# grbl_nano_my_clone_PR3.net
KiCad netlist of a schematic drawn in EAGLE
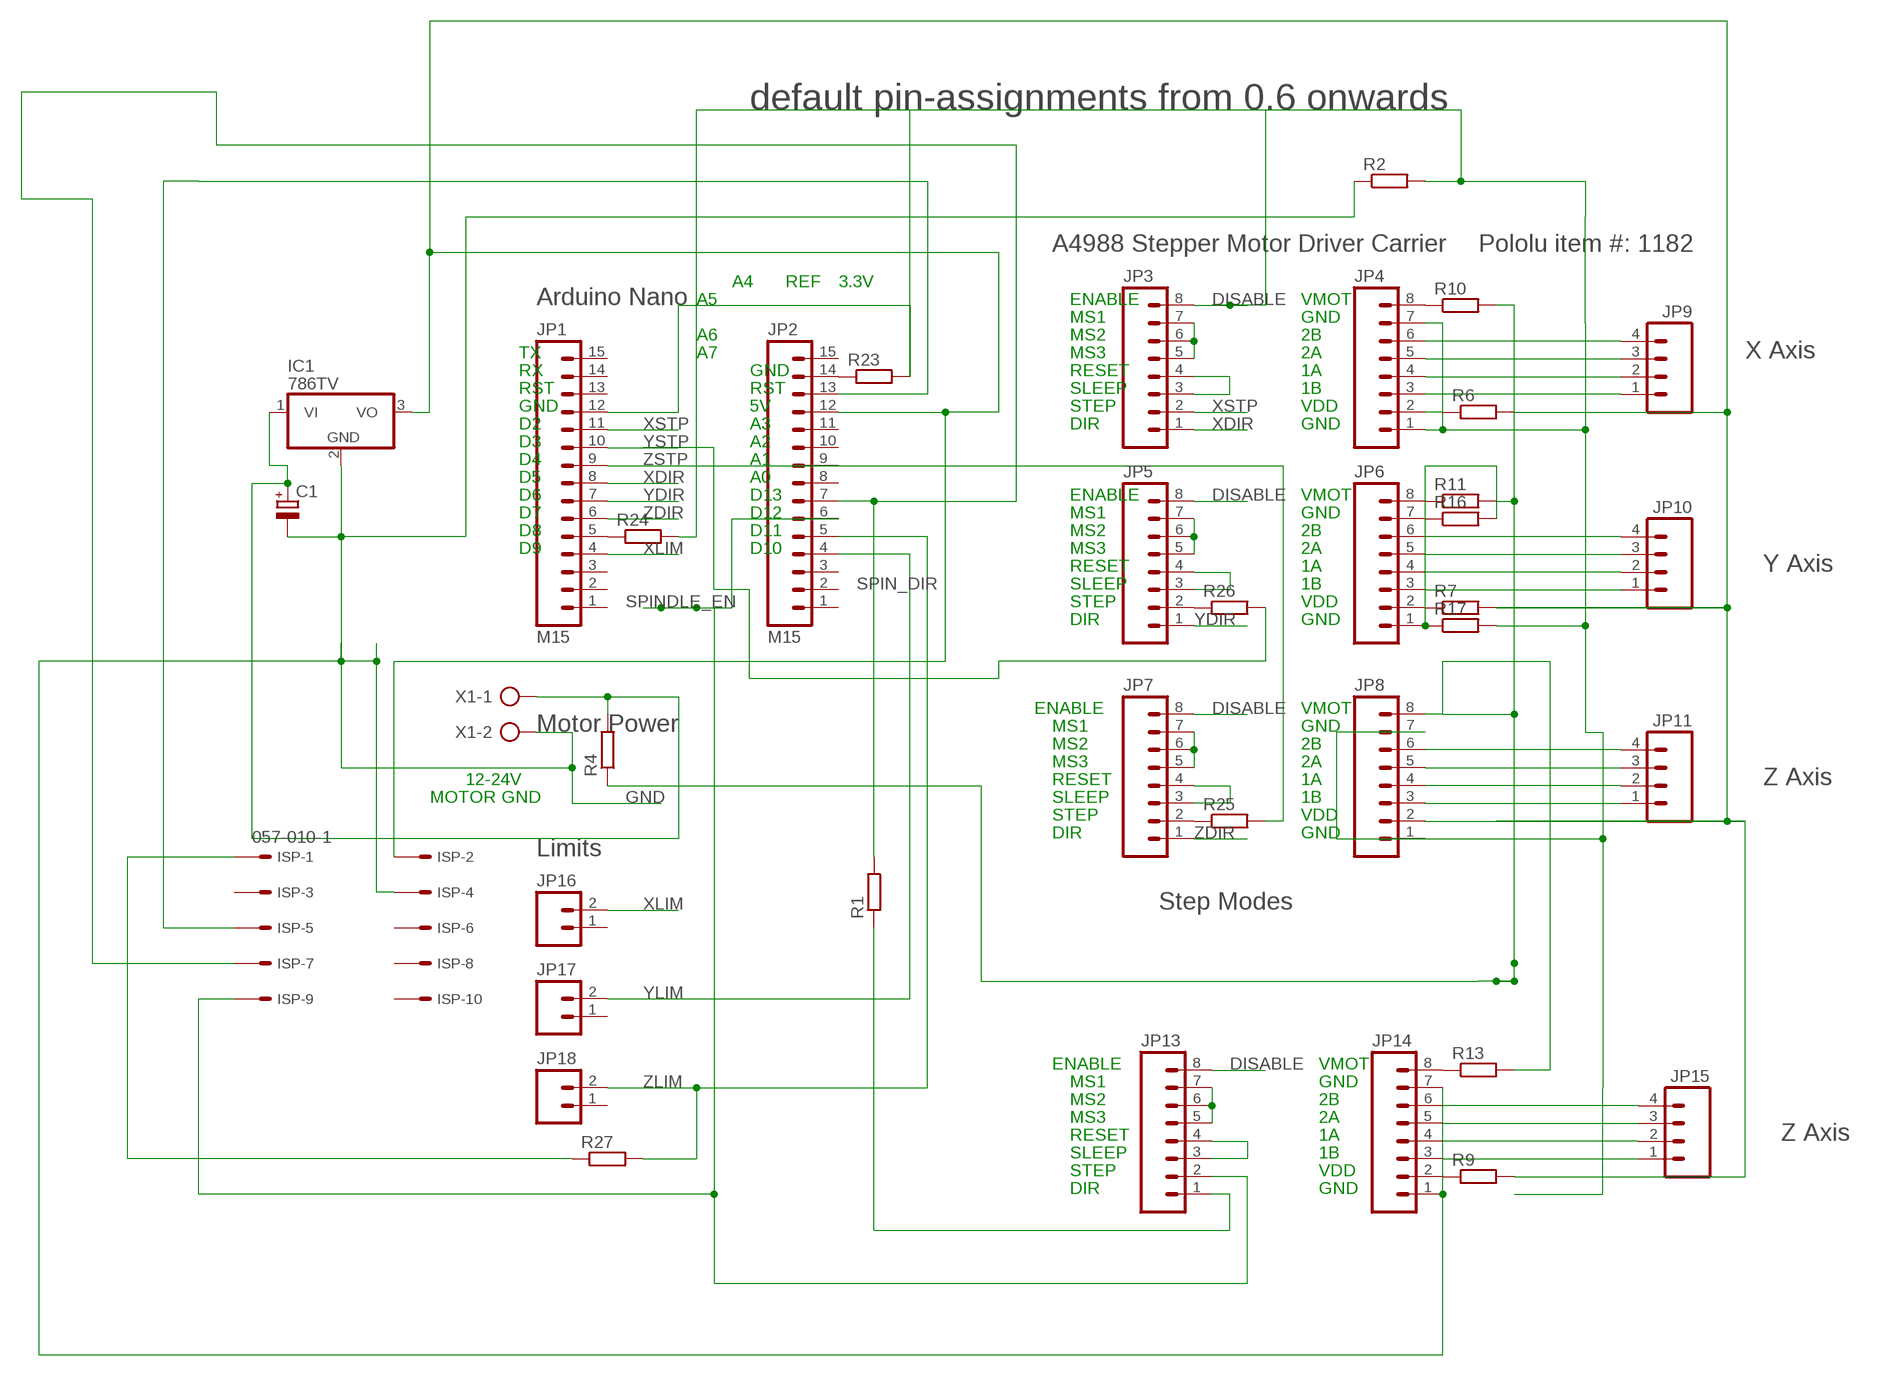
[diagram p0: schematic, sheet 1]

(export (version "E")
  (design (tool "Eeschema 10.0.6"))
  (components
    (comp (ref "C1")
      (value "CPOL-EUE3.5-8")
      (footprint "eagle-import:E3,5-8")
      (libsource (lib "eagle-import") (part "CPOL-EUE3.5-8"))
    )
    (comp (ref "IC1")
      (value "786TV")
      (footprint "eagle-import:TO220V")
      (libsource (lib "eagle-import") (part "78TV6"))
    )
    (comp (ref "ISP")
      (value "057-010-1")
      (footprint "eagle-import:057-010-1")
      (libsource (lib "eagle-import") (part "057-010-1"))
    )
    (comp (ref "JP1")
      (value "M15")
      (footprint "eagle-import:1X15")
      (libsource (lib "eagle-import") (part "M15"))
    )
    (comp (ref "JP2")
      (value "M15")
      (footprint "eagle-import:1X15")
      (libsource (lib "eagle-import") (part "M15"))
    )
    (comp (ref "JP3")
      (value "M08LONGPADS")
      (footprint "eagle-import:1X08_LONGPADS")
      (libsource (lib "eagle-import") (part "M08LONGPADS"))
    )
    (comp (ref "JP4")
      (value "M08LONGPADS")
      (footprint "eagle-import:1X08_LONGPADS")
      (libsource (lib "eagle-import") (part "M08LONGPADS"))
    )
    (comp (ref "JP5")
      (value "M08LONGPADS")
      (footprint "eagle-import:1X08_LONGPADS")
      (libsource (lib "eagle-import") (part "M08LONGPADS"))
    )
    (comp (ref "JP6")
      (value "M08LONGPADS")
      (footprint "eagle-import:1X08_LONGPADS")
      (libsource (lib "eagle-import") (part "M08LONGPADS"))
    )
    (comp (ref "JP7")
      (value "M08LONGPADS")
      (footprint "eagle-import:1X08_LONGPADS")
      (libsource (lib "eagle-import") (part "M08LONGPADS"))
    )
    (comp (ref "JP8")
      (value "M08LONGPADS")
      (footprint "eagle-import:1X08_LONGPADS")
      (libsource (lib "eagle-import") (part "M08LONGPADS"))
    )
    (comp (ref "JP9")
      (value "M04LONGPADS")
      (footprint "eagle-import:1X04_LONGPADS")
      (libsource (lib "eagle-import") (part "M04LONGPADS"))
    )
    (comp (ref "JP10")
      (value "M04LONGPADS")
      (footprint "eagle-import:1X04_LONGPADS")
      (libsource (lib "eagle-import") (part "M04LONGPADS"))
    )
    (comp (ref "JP11")
      (value "M04LONGPADS")
      (footprint "eagle-import:1X04_LONGPADS")
      (libsource (lib "eagle-import") (part "M04LONGPADS"))
    )
    (comp (ref "JP13")
      (value "M08LONGPADS")
      (footprint "eagle-import:1X08_LONGPADS")
      (libsource (lib "eagle-import") (part "M08LONGPADS"))
    )
    (comp (ref "JP14")
      (value "M08LONGPADS")
      (footprint "eagle-import:1X08_LONGPADS")
      (libsource (lib "eagle-import") (part "M08LONGPADS"))
    )
    (comp (ref "JP15")
      (value "M04LONGPADS")
      (footprint "eagle-import:1X04_LONGPADS")
      (libsource (lib "eagle-import") (part "M04LONGPADS"))
    )
    (comp (ref "JP16")
      (value "M02LOCK_LONGPADS")
      (footprint "eagle-import:1X02_LOCK_LONGPADS")
      (libsource (lib "eagle-import") (part "M02LOCK_LONGPADS"))
    )
    (comp (ref "JP17")
      (value "M02LOCK_LONGPADS")
      (footprint "eagle-import:1X02_LOCK_LONGPADS")
      (libsource (lib "eagle-import") (part "M02LOCK_LONGPADS"))
    )
    (comp (ref "JP18")
      (value "M02LOCK_LONGPADS")
      (footprint "eagle-import:1X02_LOCK_LONGPADS")
      (libsource (lib "eagle-import") (part "M02LOCK_LONGPADS"))
    )
    (comp (ref "R1")
      (value "R-EU_0207/15")
      (footprint "eagle-import:0207_15")
      (libsource (lib "eagle-import") (part "R-EU_0207/15"))
    )
    (comp (ref "R2")
      (value "R-EU_0207/15")
      (footprint "eagle-import:0207_15")
      (libsource (lib "eagle-import") (part "R-EU_0207/15"))
    )
    (comp (ref "R4")
      (value "R-EU_0207/12")
      (footprint "eagle-import:0207_12")
      (libsource (lib "eagle-import") (part "R-EU_0207/12"))
    )
    (comp (ref "R6")
      (value "R-EU_0207/15")
      (footprint "eagle-import:0207_15")
      (libsource (lib "eagle-import") (part "R-EU_0207/15"))
    )
    (comp (ref "R7")
      (value "R-EU_0207/15")
      (footprint "eagle-import:0207_15")
      (libsource (lib "eagle-import") (part "R-EU_0207/15"))
    )
    (comp (ref "R9")
      (value "R-EU_0207/15")
      (footprint "eagle-import:0207_15")
      (libsource (lib "eagle-import") (part "R-EU_0207/15"))
    )
    (comp (ref "R10")
      (value "R-EU_0207/7")
      (footprint "eagle-import:0207_7")
      (libsource (lib "eagle-import") (part "R-EU_0207/7"))
    )
    (comp (ref "R11")
      (value "R-EU_0207/7")
      (footprint "eagle-import:0207_7")
      (libsource (lib "eagle-import") (part "R-EU_0207/7"))
    )
    (comp (ref "R13")
      (value "R-EU_0207/15")
      (footprint "eagle-import:0207_15")
      (libsource (lib "eagle-import") (part "R-EU_0207/15"))
    )
    (comp (ref "R16")
      (value "R-EU_0207/12")
      (footprint "eagle-import:0207_12")
      (libsource (lib "eagle-import") (part "R-EU_0207/12"))
    )
    (comp (ref "R17")
      (value "R-EU_0207/12")
      (footprint "eagle-import:0207_12")
      (libsource (lib "eagle-import") (part "R-EU_0207/12"))
    )
    (comp (ref "R23")
      (value "R-EU_0207/15")
      (footprint "eagle-import:0207_15")
      (libsource (lib "eagle-import") (part "R-EU_0207/15"))
    )
    (comp (ref "R24")
      (value "R-EU_0207/15")
      (footprint "eagle-import:0207_15")
      (libsource (lib "eagle-import") (part "R-EU_0207/15"))
    )
    (comp (ref "R25")
      (value "R-EU_0207/15")
      (footprint "eagle-import:0207_15")
      (libsource (lib "eagle-import") (part "R-EU_0207/15"))
    )
    (comp (ref "R26")
      (value "R-EU_0207/15")
      (footprint "eagle-import:0207_15")
      (libsource (lib "eagle-import") (part "R-EU_0207/15"))
    )
    (comp (ref "R27")
      (value "R-EU_0207/15")
      (footprint "eagle-import:0207_15")
      (libsource (lib "eagle-import") (part "R-EU_0207/15"))
    )
    (comp (ref "X1")
      (value "AK300/2")
      (footprint "eagle-import:AK300_2")
      (libsource (lib "eagle-import") (part "AK300/2"))
    )
  )
  (nets
    (net (code "1") (name "/DISABLE") (class "Default")
      (node (ref "JP13") (pin "8") (pinfunction "8_8") (pintype "passive"))
      (node (ref "JP3") (pin "8") (pinfunction "8_8") (pintype "passive"))
      (node (ref "JP5") (pin "8") (pinfunction "8_8") (pintype "passive"))
      (node (ref "JP7") (pin "8") (pinfunction "8_8") (pintype "passive"))
      (node (ref "R24") (pin "2") (pinfunction "2_2") (pintype "passive"))
    )
    (net (code "2") (name "/GND") (class "Default")
      (node (ref "C1") (pin "-") (pinfunction "-_-") (pintype "passive"))
      (node (ref "IC1") (pin "2") (pinfunction "GND_2") (pintype "passive"))
      (node (ref "ISP") (pin "4") (pinfunction "S_4") (pintype "passive"))
      (node (ref "JP14") (pin "1") (pinfunction "1_1") (pintype "passive"))
      (node (ref "JP14") (pin "7") (pinfunction "7_7") (pintype "passive"))
      (node (ref "R2") (pin "1") (pinfunction "1_1") (pintype "passive"))
      (node (ref "X1") (pin "2") (pinfunction "KL_2") (pintype "passive"))
    )
    (net (code "3") (name "/SPINDLE_EN") (class "Default")
      (node (ref "ISP") (pin "9") (pinfunction "S_9") (pintype "passive"))
      (node (ref "JP13") (pin "2") (pinfunction "2_2") (pintype "passive"))
      (node (ref "JP2") (pin "6") (pinfunction "6_6") (pintype "passive"))
    )
    (net (code "5") (name "/SPIN_DIR") (class "Default")
      (node (ref "ISP") (pin "7") (pinfunction "S_7") (pintype "passive"))
      (node (ref "JP2") (pin "7") (pinfunction "7_7") (pintype "passive"))
      (node (ref "R1") (pin "2") (pinfunction "2_2") (pintype "passive"))
    )
    (net (code "6") (name "/XDIR") (class "Default")
      (node (ref "JP1") (pin "8") (pinfunction "8_8") (pintype "passive"))
      (node (ref "JP3") (pin "1") (pinfunction "1_1") (pintype "passive"))
    )
    (net (code "7") (name "/XLIM") (class "Default")
      (node (ref "JP1") (pin "4") (pinfunction "4_4") (pintype "passive"))
      (node (ref "JP16") (pin "2") (pinfunction "2_2") (pintype "passive"))
    )
    (net (code "8") (name "/XSTP") (class "Default")
      (node (ref "JP1") (pin "11") (pinfunction "11_11") (pintype "passive"))
      (node (ref "JP3") (pin "2") (pinfunction "2_2") (pintype "passive"))
    )
    (net (code "9") (name "/YDIR") (class "Default")
      (node (ref "JP1") (pin "7") (pinfunction "7_7") (pintype "passive"))
      (node (ref "JP5") (pin "1") (pinfunction "1_1") (pintype "passive"))
    )
    (net (code "10") (name "/YLIM") (class "Default")
      (node (ref "JP17") (pin "2") (pinfunction "2_2") (pintype "passive"))
      (node (ref "JP2") (pin "4") (pinfunction "4_4") (pintype "passive"))
    )
    (net (code "11") (name "/YSTP") (class "Default")
      (node (ref "JP1") (pin "10") (pinfunction "10_10") (pintype "passive"))
      (node (ref "R26") (pin "2") (pinfunction "2_2") (pintype "passive"))
    )
    (net (code "12") (name "/ZDIR") (class "Default")
      (node (ref "JP1") (pin "6") (pinfunction "6_6") (pintype "passive"))
      (node (ref "JP7") (pin "1") (pinfunction "1_1") (pintype "passive"))
    )
    (net (code "13") (name "/ZLIM") (class "Default")
      (node (ref "JP18") (pin "2") (pinfunction "2_2") (pintype "passive"))
      (node (ref "JP2") (pin "5") (pinfunction "5_5") (pintype "passive"))
      (node (ref "R27") (pin "2") (pinfunction "2_2") (pintype "passive"))
    )
    (net (code "14") (name "/ZSTP") (class "Default")
      (node (ref "JP1") (pin "9") (pinfunction "9_9") (pintype "passive"))
      (node (ref "R25") (pin "2") (pinfunction "2_2") (pintype "passive"))
    )
    (net (code "15") (name "Net-(IC1-VI)") (class "Default")
      (node (ref "C1") (pin "+") (pinfunction "+_+") (pintype "passive"))
      (node (ref "IC1") (pin "1") (pinfunction "VI_1") (pintype "input"))
      (node (ref "R4") (pin "2") (pinfunction "2_2") (pintype "passive"))
      (node (ref "X1") (pin "1") (pinfunction "KL_1") (pintype "passive"))
    )
    (net (code "16") (name "Net-(IC1-VO)") (class "Default")
      (node (ref "IC1") (pin "3") (pinfunction "VO_3") (pintype "passive"))
      (node (ref "ISP") (pin "2") (pinfunction "S_2") (pintype "passive"))
      (node (ref "JP2") (pin "12") (pinfunction "12_12") (pintype "passive"))
      (node (ref "JP8") (pin "2") (pinfunction "2_2") (pintype "passive"))
      (node (ref "R6") (pin "2") (pinfunction "2_2") (pintype "passive"))
      (node (ref "R7") (pin "2") (pinfunction "2_2") (pintype "passive"))
      (node (ref "R9") (pin "2") (pinfunction "2_2") (pintype "passive"))
    )
    (net (code "17") (name "Net-(ISPA-S)") (class "Default")
      (node (ref "ISP") (pin "1") (pinfunction "S_1") (pintype "passive"))
      (node (ref "R27") (pin "1") (pinfunction "1_1") (pintype "passive"))
    )
    (net (code "18") (name "Net-(ISPF-S)") (class "Default")
      (node (ref "ISP") (pin "5") (pinfunction "S_5") (pintype "passive"))
      (node (ref "JP2") (pin "13") (pinfunction "13_13") (pintype "passive"))
    )
    (net (code "19") (name "Net-(JP1-Pad5)") (class "Default")
      (node (ref "JP1") (pin "5") (pinfunction "5_5") (pintype "passive"))
      (node (ref "R24") (pin "1") (pinfunction "1_1") (pintype "passive"))
    )
    (net (code "20") (name "Net-(JP1-Pad12)") (class "Default")
      (node (ref "JP1") (pin "12") (pinfunction "12_12") (pintype "passive"))
      (node (ref "JP4") (pin "1") (pinfunction "1_1") (pintype "passive"))
      (node (ref "JP4") (pin "7") (pinfunction "7_7") (pintype "passive"))
      (node (ref "JP8") (pin "1") (pinfunction "1_1") (pintype "passive"))
      (node (ref "JP8") (pin "7") (pinfunction "7_7") (pintype "passive"))
      (node (ref "R17") (pin "2") (pinfunction "2_2") (pintype "passive"))
      (node (ref "R2") (pin "2") (pinfunction "2_2") (pintype "passive"))
      (node (ref "R23") (pin "2") (pinfunction "2_2") (pintype "passive"))
    )
    (net (code "21") (name "Net-(JP2-Pad14)") (class "Default")
      (node (ref "JP2") (pin "14") (pinfunction "14_14") (pintype "passive"))
      (node (ref "R23") (pin "1") (pinfunction "1_1") (pintype "passive"))
    )
    (net (code "22") (name "Net-(JP3-Pad3)") (class "Default")
      (node (ref "JP3") (pin "3") (pinfunction "3_3") (pintype "passive"))
      (node (ref "JP3") (pin "4") (pinfunction "4_4") (pintype "passive"))
    )
    (net (code "23") (name "Net-(JP3-Pad5)") (class "Default")
      (node (ref "JP3") (pin "5") (pinfunction "5_5") (pintype "passive"))
      (node (ref "JP3") (pin "6") (pinfunction "6_6") (pintype "passive"))
      (node (ref "JP3") (pin "7") (pinfunction "7_7") (pintype "passive"))
    )
    (net (code "24") (name "Net-(JP4-Pad2)") (class "Default")
      (node (ref "JP4") (pin "2") (pinfunction "2_2") (pintype "passive"))
      (node (ref "R6") (pin "1") (pinfunction "1_1") (pintype "passive"))
    )
    (net (code "25") (name "Net-(JP4-Pad3)") (class "Default")
      (node (ref "JP4") (pin "3") (pinfunction "3_3") (pintype "passive"))
      (node (ref "JP9") (pin "1") (pinfunction "1_1") (pintype "passive"))
    )
    (net (code "26") (name "Net-(JP4-Pad4)") (class "Default")
      (node (ref "JP4") (pin "4") (pinfunction "4_4") (pintype "passive"))
      (node (ref "JP9") (pin "2") (pinfunction "2_2") (pintype "passive"))
    )
    (net (code "27") (name "Net-(JP4-Pad5)") (class "Default")
      (node (ref "JP4") (pin "5") (pinfunction "5_5") (pintype "passive"))
      (node (ref "JP9") (pin "3") (pinfunction "3_3") (pintype "passive"))
    )
    (net (code "28") (name "Net-(JP4-Pad6)") (class "Default")
      (node (ref "JP4") (pin "6") (pinfunction "6_6") (pintype "passive"))
      (node (ref "JP9") (pin "4") (pinfunction "4_4") (pintype "passive"))
    )
    (net (code "29") (name "Net-(JP4-Pad8)") (class "Default")
      (node (ref "JP4") (pin "8") (pinfunction "8_8") (pintype "passive"))
      (node (ref "R10") (pin "1") (pinfunction "1_1") (pintype "passive"))
    )
    (net (code "30") (name "Net-(JP5-Pad2)") (class "Default")
      (node (ref "JP5") (pin "2") (pinfunction "2_2") (pintype "passive"))
      (node (ref "R26") (pin "1") (pinfunction "1_1") (pintype "passive"))
    )
    (net (code "31") (name "Net-(JP5-Pad3)") (class "Default")
      (node (ref "JP5") (pin "3") (pinfunction "3_3") (pintype "passive"))
      (node (ref "JP5") (pin "4") (pinfunction "4_4") (pintype "passive"))
    )
    (net (code "32") (name "Net-(JP5-Pad5)") (class "Default")
      (node (ref "JP5") (pin "5") (pinfunction "5_5") (pintype "passive"))
      (node (ref "JP5") (pin "6") (pinfunction "6_6") (pintype "passive"))
      (node (ref "JP5") (pin "7") (pinfunction "7_7") (pintype "passive"))
    )
    (net (code "33") (name "Net-(JP6-Pad1)") (class "Default")
      (node (ref "JP6") (pin "1") (pinfunction "1_1") (pintype "passive"))
      (node (ref "R16") (pin "2") (pinfunction "2_2") (pintype "passive"))
      (node (ref "R17") (pin "1") (pinfunction "1_1") (pintype "passive"))
    )
    (net (code "34") (name "Net-(JP6-Pad2)") (class "Default")
      (node (ref "JP6") (pin "2") (pinfunction "2_2") (pintype "passive"))
      (node (ref "R7") (pin "1") (pinfunction "1_1") (pintype "passive"))
    )
    (net (code "35") (name "Net-(JP6-Pad7)") (class "Default")
      (node (ref "JP6") (pin "7") (pinfunction "7_7") (pintype "passive"))
      (node (ref "R16") (pin "1") (pinfunction "1_1") (pintype "passive"))
    )
    (net (code "36") (name "Net-(JP6-Pad8)") (class "Default")
      (node (ref "JP6") (pin "8") (pinfunction "8_8") (pintype "passive"))
      (node (ref "R11") (pin "1") (pinfunction "1_1") (pintype "passive"))
    )
    (net (code "37") (name "Net-(JP7-Pad2)") (class "Default")
      (node (ref "JP7") (pin "2") (pinfunction "2_2") (pintype "passive"))
      (node (ref "R25") (pin "1") (pinfunction "1_1") (pintype "passive"))
    )
    (net (code "38") (name "Net-(JP7-Pad3)") (class "Default")
      (node (ref "JP7") (pin "3") (pinfunction "3_3") (pintype "passive"))
      (node (ref "JP7") (pin "4") (pinfunction "4_4") (pintype "passive"))
    )
    (net (code "39") (name "Net-(JP7-Pad5)") (class "Default")
      (node (ref "JP7") (pin "5") (pinfunction "5_5") (pintype "passive"))
      (node (ref "JP7") (pin "6") (pinfunction "6_6") (pintype "passive"))
      (node (ref "JP7") (pin "7") (pinfunction "7_7") (pintype "passive"))
    )
    (net (code "40") (name "Net-(JP8-Pad8)") (class "Default")
      (node (ref "JP8") (pin "8") (pinfunction "8_8") (pintype "passive"))
      (node (ref "R10") (pin "2") (pinfunction "2_2") (pintype "passive"))
      (node (ref "R11") (pin "2") (pinfunction "2_2") (pintype "passive"))
      (node (ref "R13") (pin "2") (pinfunction "2_2") (pintype "passive"))
      (node (ref "R4") (pin "1") (pinfunction "1_1") (pintype "passive"))
    )
    (net (code "41") (name "Net-(JP10-Pad1)") (class "Default")
      (node (ref "JP10") (pin "1") (pinfunction "1_1") (pintype "passive"))
      (node (ref "JP6") (pin "3") (pinfunction "3_3") (pintype "passive"))
    )
    (net (code "42") (name "Net-(JP10-Pad2)") (class "Default")
      (node (ref "JP10") (pin "2") (pinfunction "2_2") (pintype "passive"))
      (node (ref "JP6") (pin "4") (pinfunction "4_4") (pintype "passive"))
    )
    (net (code "43") (name "Net-(JP10-Pad3)") (class "Default")
      (node (ref "JP10") (pin "3") (pinfunction "3_3") (pintype "passive"))
      (node (ref "JP6") (pin "5") (pinfunction "5_5") (pintype "passive"))
    )
    (net (code "44") (name "Net-(JP10-Pad4)") (class "Default")
      (node (ref "JP10") (pin "4") (pinfunction "4_4") (pintype "passive"))
      (node (ref "JP6") (pin "6") (pinfunction "6_6") (pintype "passive"))
    )
    (net (code "45") (name "Net-(JP11-Pad1)") (class "Default")
      (node (ref "JP11") (pin "1") (pinfunction "1_1") (pintype "passive"))
      (node (ref "JP8") (pin "3") (pinfunction "3_3") (pintype "passive"))
    )
    (net (code "46") (name "Net-(JP11-Pad2)") (class "Default")
      (node (ref "JP11") (pin "2") (pinfunction "2_2") (pintype "passive"))
      (node (ref "JP8") (pin "4") (pinfunction "4_4") (pintype "passive"))
    )
    (net (code "47") (name "Net-(JP11-Pad3)") (class "Default")
      (node (ref "JP11") (pin "3") (pinfunction "3_3") (pintype "passive"))
      (node (ref "JP8") (pin "5") (pinfunction "5_5") (pintype "passive"))
    )
    (net (code "48") (name "Net-(JP11-Pad4)") (class "Default")
      (node (ref "JP11") (pin "4") (pinfunction "4_4") (pintype "passive"))
      (node (ref "JP8") (pin "6") (pinfunction "6_6") (pintype "passive"))
    )
    (net (code "49") (name "Net-(JP13-Pad1)") (class "Default")
      (node (ref "JP13") (pin "1") (pinfunction "1_1") (pintype "passive"))
      (node (ref "R1") (pin "1") (pinfunction "1_1") (pintype "passive"))
    )
    (net (code "50") (name "Net-(JP13-Pad3)") (class "Default")
      (node (ref "JP13") (pin "3") (pinfunction "3_3") (pintype "passive"))
      (node (ref "JP13") (pin "4") (pinfunction "4_4") (pintype "passive"))
    )
    (net (code "51") (name "Net-(JP13-Pad5)") (class "Default")
      (node (ref "JP13") (pin "5") (pinfunction "5_5") (pintype "passive"))
      (node (ref "JP13") (pin "6") (pinfunction "6_6") (pintype "passive"))
      (node (ref "JP13") (pin "7") (pinfunction "7_7") (pintype "passive"))
    )
    (net (code "52") (name "Net-(JP14-Pad2)") (class "Default")
      (node (ref "JP14") (pin "2") (pinfunction "2_2") (pintype "passive"))
      (node (ref "R9") (pin "1") (pinfunction "1_1") (pintype "passive"))
    )
    (net (code "53") (name "Net-(JP14-Pad3)") (class "Default")
      (node (ref "JP14") (pin "3") (pinfunction "3_3") (pintype "passive"))
      (node (ref "JP15") (pin "1") (pinfunction "1_1") (pintype "passive"))
    )
    (net (code "54") (name "Net-(JP14-Pad4)") (class "Default")
      (node (ref "JP14") (pin "4") (pinfunction "4_4") (pintype "passive"))
      (node (ref "JP15") (pin "2") (pinfunction "2_2") (pintype "passive"))
    )
    (net (code "55") (name "Net-(JP14-Pad5)") (class "Default")
      (node (ref "JP14") (pin "5") (pinfunction "5_5") (pintype "passive"))
      (node (ref "JP15") (pin "3") (pinfunction "3_3") (pintype "passive"))
    )
    (net (code "56") (name "Net-(JP14-Pad6)") (class "Default")
      (node (ref "JP14") (pin "6") (pinfunction "6_6") (pintype "passive"))
      (node (ref "JP15") (pin "4") (pinfunction "4_4") (pintype "passive"))
    )
    (net (code "57") (name "Net-(JP14-Pad8)") (class "Default")
      (node (ref "JP14") (pin "8") (pinfunction "8_8") (pintype "passive"))
      (node (ref "R13") (pin "1") (pinfunction "1_1") (pintype "passive"))
    )
    (net (code "58") (name "unconnected-(ISPB-S-Pad10)") (class "Default")
      (node (ref "ISP") (pin "10") (pinfunction "S_10") (pintype "passive"))
    )
    (net (code "59") (name "unconnected-(ISPD-S-Pad3)") (class "Default")
      (node (ref "ISP") (pin "3") (pinfunction "S_3") (pintype "passive"))
    )
    (net (code "60") (name "unconnected-(ISPG-S-Pad6)") (class "Default")
      (node (ref "ISP") (pin "6") (pinfunction "S_6") (pintype "passive"))
    )
    (net (code "61") (name "unconnected-(ISPI-S-Pad8)") (class "Default")
      (node (ref "ISP") (pin "8") (pinfunction "S_8") (pintype "passive"))
    )
    (net (code "62") (name "unconnected-(JP1-Pad1)") (class "Default")
      (node (ref "JP1") (pin "1") (pinfunction "1_1") (pintype "passive"))
    )
    (net (code "63") (name "unconnected-(JP1-Pad2)") (class "Default")
      (node (ref "JP1") (pin "2") (pinfunction "2_2") (pintype "passive"))
    )
    (net (code "64") (name "unconnected-(JP1-Pad3)") (class "Default")
      (node (ref "JP1") (pin "3") (pinfunction "3_3") (pintype "passive"))
    )
    (net (code "65") (name "unconnected-(JP1-Pad13)") (class "Default")
      (node (ref "JP1") (pin "13") (pinfunction "13_13") (pintype "passive"))
    )
    (net (code "66") (name "unconnected-(JP1-Pad14)") (class "Default")
      (node (ref "JP1") (pin "14") (pinfunction "14_14") (pintype "passive"))
    )
    (net (code "67") (name "unconnected-(JP1-Pad15)") (class "Default")
      (node (ref "JP1") (pin "15") (pinfunction "15_15") (pintype "passive"))
    )
    (net (code "68") (name "unconnected-(JP2-Pad1)") (class "Default")
      (node (ref "JP2") (pin "1") (pinfunction "1_1") (pintype "passive"))
    )
    (net (code "69") (name "unconnected-(JP2-Pad2)") (class "Default")
      (node (ref "JP2") (pin "2") (pinfunction "2_2") (pintype "passive"))
    )
    (net (code "70") (name "unconnected-(JP2-Pad3)") (class "Default")
      (node (ref "JP2") (pin "3") (pinfunction "3_3") (pintype "passive"))
    )
    (net (code "71") (name "unconnected-(JP2-Pad8)") (class "Default")
      (node (ref "JP2") (pin "8") (pinfunction "8_8") (pintype "passive"))
    )
    (net (code "72") (name "unconnected-(JP2-Pad9)") (class "Default")
      (node (ref "JP2") (pin "9") (pinfunction "9_9") (pintype "passive"))
    )
    (net (code "73") (name "unconnected-(JP2-Pad10)") (class "Default")
      (node (ref "JP2") (pin "10") (pinfunction "10_10") (pintype "passive"))
    )
    (net (code "74") (name "unconnected-(JP2-Pad11)") (class "Default")
      (node (ref "JP2") (pin "11") (pinfunction "11_11") (pintype "passive"))
    )
    (net (code "75") (name "unconnected-(JP2-Pad15)") (class "Default")
      (node (ref "JP2") (pin "15") (pinfunction "15_15") (pintype "passive"))
    )
    (net (code "76") (name "unconnected-(JP16-Pad1)") (class "Default")
      (node (ref "JP16") (pin "1") (pinfunction "1_1") (pintype "passive"))
    )
    (net (code "77") (name "unconnected-(JP17-Pad1)") (class "Default")
      (node (ref "JP17") (pin "1") (pinfunction "1_1") (pintype "passive"))
    )
    (net (code "78") (name "unconnected-(JP18-Pad1)") (class "Default")
      (node (ref "JP18") (pin "1") (pinfunction "1_1") (pintype "passive"))
    )
  )
)
